# design.net
KiCad netlist of a schematic drawn in EAGLE
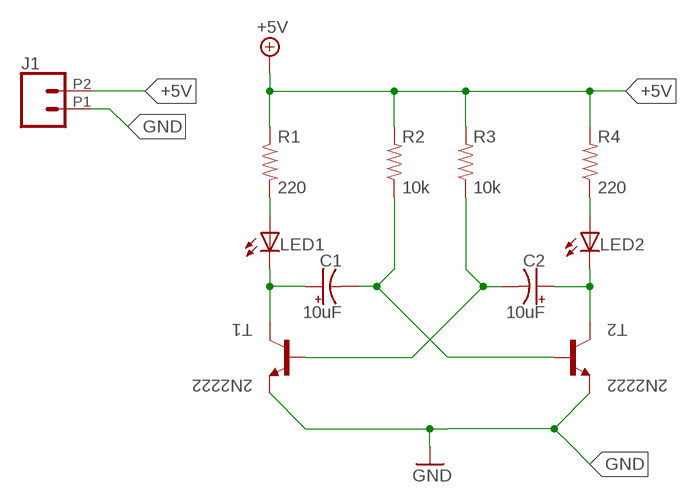
[diagram p0: schematic, sheet 1]

(export (version "E")
  (design (tool "Eeschema 10.0.6"))
  (components
    (comp (ref "C1")
      (value "10uF")
      (footprint "eagle-import:CPOL-RADIAL-2.5MM-5MM")
      (libsource (lib "eagle-import") (part "10UF-POLAR-RADIAL-2.5MM-25V-20%"))
    )
    (comp (ref "C2")
      (value "10uF")
      (footprint "eagle-import:CPOL-RADIAL-2.5MM-5MM")
      (libsource (lib "eagle-import") (part "10UF-POLAR-RADIAL-2.5MM-25V-20%"))
    )
    (comp (ref "J1")
      (value "CONN_022.54MM_SCREWTERM")
      (footprint "eagle-import:1X02_2.54_SCREWTERM")
      (libsource (lib "eagle-import") (part "CONN_022.54MM_SCREWTERM"))
    )
    (comp (ref "LED1")
      (value "LED5MM")
      (footprint "eagle-import:LED5MM")
      (libsource (lib "eagle-import") (part "LED5MM"))
    )
    (comp (ref "LED2")
      (value "LED5MM")
      (footprint "eagle-import:LED5MM")
      (libsource (lib "eagle-import") (part "LED5MM"))
    )
    (comp (ref "R1")
      (value "220")
      (footprint "eagle-import:AXIAL-0.3")
      (libsource (lib "eagle-import") (part "100OHM-HORIZ-1/4W-1%"))
    )
    (comp (ref "R2")
      (value "10k")
      (footprint "eagle-import:AXIAL-0.3")
      (libsource (lib "eagle-import") (part "100OHM-HORIZ-1/4W-1%"))
    )
    (comp (ref "R3")
      (value "10k")
      (footprint "eagle-import:AXIAL-0.3")
      (libsource (lib "eagle-import") (part "100OHM-HORIZ-1/4W-1%"))
    )
    (comp (ref "R4")
      (value "220")
      (footprint "eagle-import:AXIAL-0.3")
      (libsource (lib "eagle-import") (part "100OHM-HORIZ-1/4W-1%"))
    )
    (comp (ref "T1")
      (value "2N2222")
      (footprint "eagle-import:TO92-EBC-OVAL")
      (libsource (lib "eagle-import") (part "2N2222"))
    )
    (comp (ref "T2")
      (value "2N2222")
      (footprint "eagle-import:TO92-EBC-OVAL")
      (libsource (lib "eagle-import") (part "2N2222"))
    )
  )
  (nets
    (net (code "1") (name "+5V") (class "Default")
      (node (ref "J1") (pin "P2") (pinfunction "2_P2") (pintype "passive"))
      (node (ref "R1") (pin "P$1") (pinfunction "1_P$1") (pintype "passive"))
      (node (ref "R2") (pin "P$2") (pinfunction "2_P$2") (pintype "passive"))
      (node (ref "R3") (pin "P$2") (pinfunction "2_P$2") (pintype "passive"))
      (node (ref "R4") (pin "P$2") (pinfunction "2_P$2") (pintype "passive"))
    )
    (net (code "2") (name "GND") (class "Default")
      (node (ref "J1") (pin "P1") (pinfunction "1_P1") (pintype "passive"))
      (node (ref "T1") (pin "E") (pinfunction "E_E") (pintype "passive"))
      (node (ref "T2") (pin "E") (pinfunction "E_E") (pintype "passive"))
    )
    (net (code "3") (name "Net-(C1-+)") (class "Default")
      (node (ref "C1") (pin "1") (pinfunction "+_1") (pintype "passive"))
      (node (ref "LED1") (pin "K") (pinfunction "C_K") (pintype "passive"))
      (node (ref "T1") (pin "C") (pinfunction "C_C") (pintype "passive"))
    )
    (net (code "4") (name "Net-(C1--)") (class "Default")
      (node (ref "C1") (pin "2") (pinfunction "-_2") (pintype "passive"))
      (node (ref "R2") (pin "P$1") (pinfunction "1_P$1") (pintype "passive"))
      (node (ref "T2") (pin "B") (pinfunction "B_B") (pintype "passive"))
    )
    (net (code "5") (name "Net-(C2-+)") (class "Default")
      (node (ref "C2") (pin "1") (pinfunction "+_1") (pintype "passive"))
      (node (ref "LED2") (pin "K") (pinfunction "C_K") (pintype "passive"))
      (node (ref "T2") (pin "C") (pinfunction "C_C") (pintype "passive"))
    )
    (net (code "6") (name "Net-(C2--)") (class "Default")
      (node (ref "C2") (pin "2") (pinfunction "-_2") (pintype "passive"))
      (node (ref "R3") (pin "P$1") (pinfunction "1_P$1") (pintype "passive"))
      (node (ref "T1") (pin "B") (pinfunction "B_B") (pintype "passive"))
    )
    (net (code "7") (name "Net-(R1-2)") (class "Default")
      (node (ref "LED1") (pin "A") (pinfunction "A_A") (pintype "passive"))
      (node (ref "R1") (pin "P$2") (pinfunction "2_P$2") (pintype "passive"))
    )
    (net (code "8") (name "Net-(R4-1)") (class "Default")
      (node (ref "LED2") (pin "A") (pinfunction "A_A") (pintype "passive"))
      (node (ref "R4") (pin "P$1") (pinfunction "1_P$1") (pintype "passive"))
    )
  )
)
